# KGGR_wD_FIX.net
KiCad netlist of a schematic drawn in EAGLE
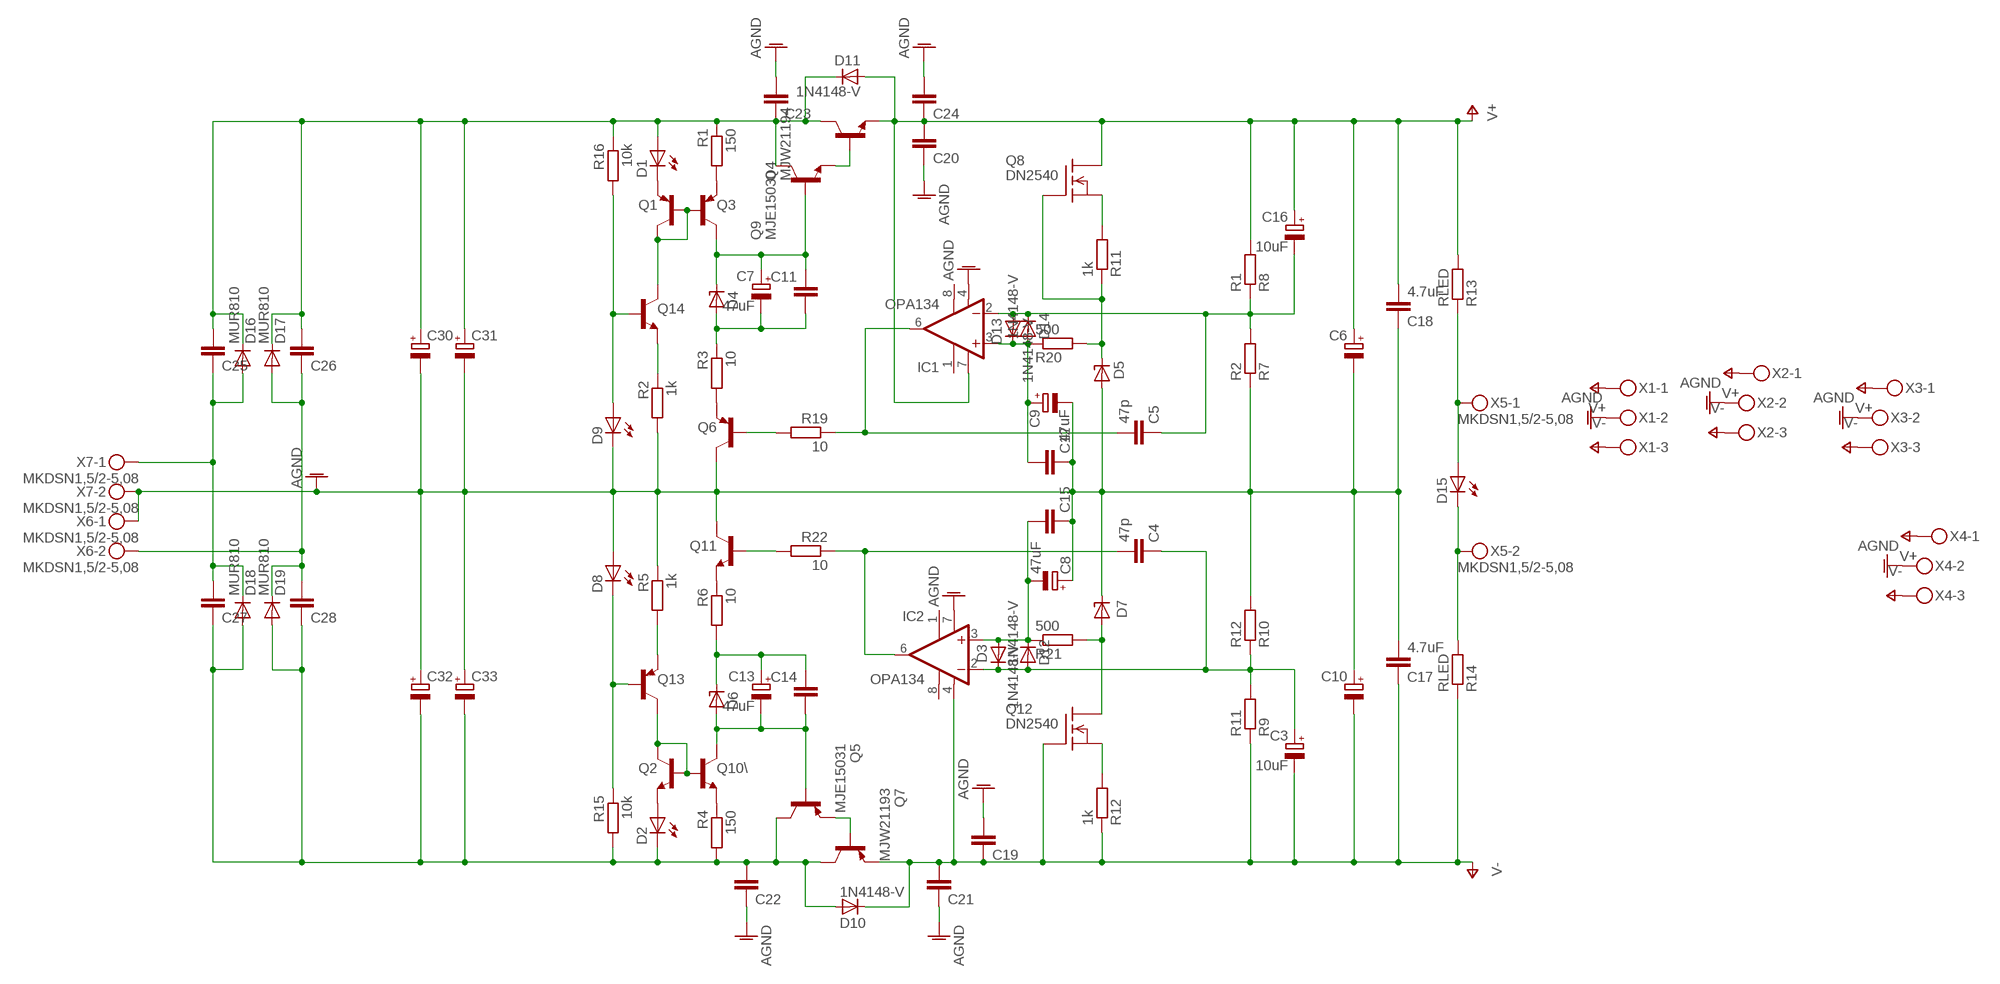
[diagram p0: schematic, sheet 1]
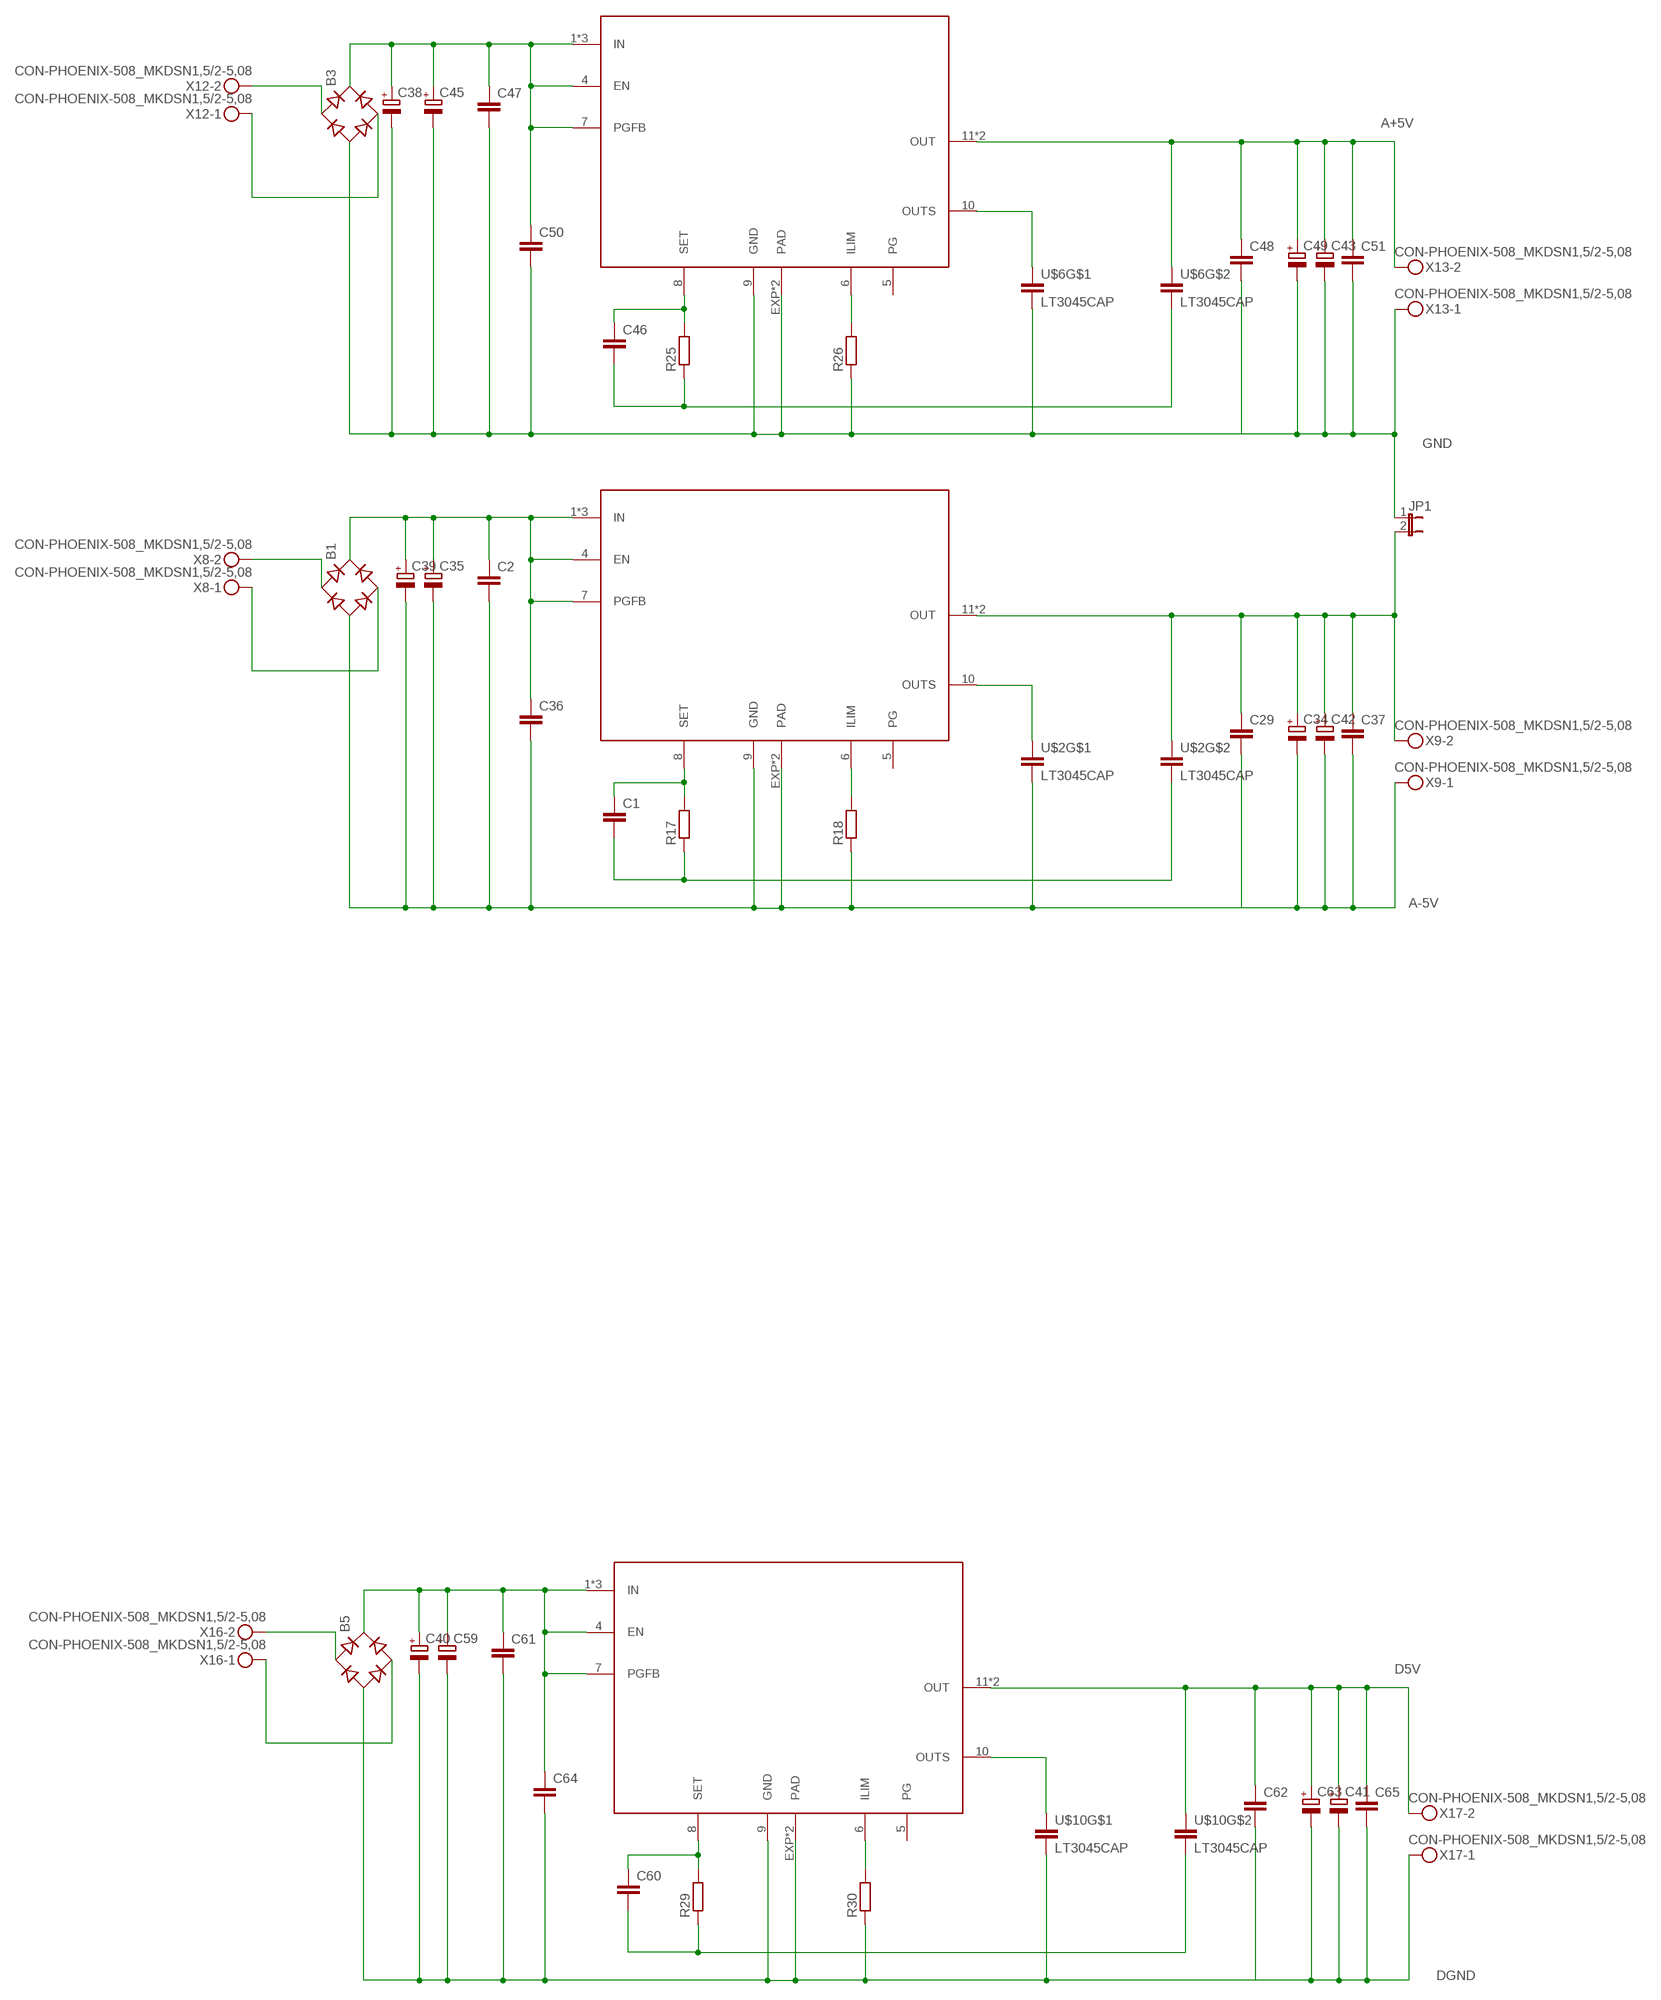
[diagram p1: schematic, sheet 2]

(export (version "E")
  (design (tool "Eeschema 10.0.6"))
  (components
    (comp (ref "C3")
      (value "10uF")
      (footprint "eagle-import:E5-8,5")
      (libsource (lib "eagle-import") (part "CPOL-EUE5-8.5"))
    )
    (comp (ref "C4")
      (value "47p")
      (footprint "eagle-import:C025_050-025X075")
      (libsource (lib "eagle-import") (part "C-EU025_050-025X075"))
    )
    (comp (ref "C5")
      (value "47p")
      (footprint "eagle-import:C025_050-025X075")
      (libsource (lib "eagle-import") (part "C-EU025_050-025X075"))
    )
    (comp (ref "C6")
      (value "CPOL-EUE7.5-18")
      (footprint "eagle-import:E7,5-18")
      (libsource (lib "eagle-import") (part "CPOL-EUE7.5-18"))
    )
    (comp (ref "C7")
      (value "47uF")
      (footprint "eagle-import:E5-8,5")
      (libsource (lib "eagle-import") (part "CPOL-EUE5-8.5"))
    )
    (comp (ref "C8")
      (value "47uF")
      (footprint "eagle-import:E5-8,5")
      (libsource (lib "eagle-import") (part "CPOL-EUE5-8.5"))
    )
    (comp (ref "C9")
      (value "47uF")
      (footprint "eagle-import:E5-8,5")
      (libsource (lib "eagle-import") (part "CPOL-EUE5-8.5"))
    )
    (comp (ref "C10")
      (value "CPOL-EUE7.5-18")
      (footprint "eagle-import:E7,5-18")
      (libsource (lib "eagle-import") (part "CPOL-EUE7.5-18"))
    )
    (comp (ref "C11")
      (value "C-EU050-035X075")
      (footprint "eagle-import:C050-035X075")
      (libsource (lib "eagle-import") (part "C-EU050-035X075"))
    )
    (comp (ref "C12")
      (value "C-EU050-035X075")
      (footprint "eagle-import:C050-035X075")
      (libsource (lib "eagle-import") (part "C-EU050-035X075"))
    )
    (comp (ref "C13")
      (value "47uF")
      (footprint "eagle-import:E5-8,5")
      (libsource (lib "eagle-import") (part "CPOL-EUE5-8.5"))
    )
    (comp (ref "C14")
      (value "C-EU050-035X075")
      (footprint "eagle-import:C050-035X075")
      (libsource (lib "eagle-import") (part "C-EU050-035X075"))
    )
    (comp (ref "C15")
      (value "C-EU050-035X075")
      (footprint "eagle-import:C050-035X075")
      (libsource (lib "eagle-import") (part "C-EU050-035X075"))
    )
    (comp (ref "C16")
      (value "10uF")
      (footprint "eagle-import:E5-8,5")
      (libsource (lib "eagle-import") (part "CPOL-EUE5-8.5"))
    )
    (comp (ref "C17")
      (value "4.7uF")
      (footprint "eagle-import:C050-075X075")
      (libsource (lib "eagle-import") (part "C-EU050-075X075"))
    )
    (comp (ref "C18")
      (value "4.7uF")
      (footprint "eagle-import:C050-075X075")
      (libsource (lib "eagle-import") (part "C-EU050-075X075"))
    )
    (comp (ref "C19")
      (value "C-EU050-035X075")
      (footprint "eagle-import:C050-035X075")
      (libsource (lib "eagle-import") (part "C-EU050-035X075"))
    )
    (comp (ref "C20")
      (value "C-EU050-035X075")
      (footprint "eagle-import:C050-035X075")
      (libsource (lib "eagle-import") (part "C-EU050-035X075"))
    )
    (comp (ref "C21")
      (value "C-EU050-035X075")
      (footprint "eagle-import:C050-035X075")
      (libsource (lib "eagle-import") (part "C-EU050-035X075"))
    )
    (comp (ref "C22")
      (value "C-EU050-075X075")
      (footprint "eagle-import:C050-075X075")
      (libsource (lib "eagle-import") (part "C-EU050-075X075"))
    )
    (comp (ref "C23")
      (value "C-EU050-075X075")
      (footprint "eagle-import:C050-075X075")
      (libsource (lib "eagle-import") (part "C-EU050-075X075"))
    )
    (comp (ref "C24")
      (value "C-EU050-035X075")
      (footprint "eagle-import:C050-035X075")
      (libsource (lib "eagle-import") (part "C-EU050-035X075"))
    )
    (comp (ref "C25")
      (value "C-EU050-035X075")
      (footprint "eagle-import:C050-035X075")
      (libsource (lib "eagle-import") (part "C-EU050-035X075"))
    )
    (comp (ref "C26")
      (value "C-EU050-035X075")
      (footprint "eagle-import:C050-035X075")
      (libsource (lib "eagle-import") (part "C-EU050-035X075"))
    )
    (comp (ref "C27")
      (value "C-EU050-035X075")
      (footprint "eagle-import:C050-035X075")
      (libsource (lib "eagle-import") (part "C-EU050-035X075"))
    )
    (comp (ref "C28")
      (value "C-EU050-035X075")
      (footprint "eagle-import:C050-035X075")
      (libsource (lib "eagle-import") (part "C-EU050-035X075"))
    )
    (comp (ref "C30")
      (value "CPOL-EUE7.5-18")
      (footprint "eagle-import:E7,5-18")
      (libsource (lib "eagle-import") (part "CPOL-EUE7.5-18"))
    )
    (comp (ref "C31")
      (value "CPOL-EUE7.5-18")
      (footprint "eagle-import:E7,5-18")
      (libsource (lib "eagle-import") (part "CPOL-EUE7.5-18"))
    )
    (comp (ref "C32")
      (value "CPOL-EUE7.5-18")
      (footprint "eagle-import:E7,5-18")
      (libsource (lib "eagle-import") (part "CPOL-EUE7.5-18"))
    )
    (comp (ref "C33")
      (value "CPOL-EUE7.5-18")
      (footprint "eagle-import:E7,5-18")
      (libsource (lib "eagle-import") (part "CPOL-EUE7.5-18"))
    )
    (comp (ref "D1")
      (value "LED5MM")
      (footprint "eagle-import:LED5MM")
      (libsource (lib "eagle-import") (part "LED5MM"))
    )
    (comp (ref "D2")
      (value "LED5MM")
      (footprint "eagle-import:LED5MM")
      (libsource (lib "eagle-import") (part "LED5MM"))
    )
    (comp (ref "D3")
      (value "1N4148-V")
      (footprint "eagle-import:1N4148")
      (libsource (lib "eagle-import") (part "1N4148-V"))
    )
    (comp (ref "D4")
      (value "1N4728")
      (footprint "eagle-import:DO41Z10")
      (libsource (lib "eagle-import") (part "1N4728"))
    )
    (comp (ref "D5")
      (value "LT1021")
      (footprint "eagle-import:DIL08")
      (libsource (lib "eagle-import") (part "LT1021-V"))
    )
    (comp (ref "D6")
      (value "1N4728")
      (footprint "eagle-import:DO41Z10")
      (libsource (lib "eagle-import") (part "1N4728"))
    )
    (comp (ref "D7")
      (value "LT1021")
      (footprint "eagle-import:DIL08")
      (libsource (lib "eagle-import") (part "LT1021-V"))
    )
    (comp (ref "D8")
      (value "LED5MM")
      (footprint "eagle-import:LED5MM")
      (libsource (lib "eagle-import") (part "LED5MM"))
    )
    (comp (ref "D9")
      (value "LED5MM")
      (footprint "eagle-import:LED5MM")
      (libsource (lib "eagle-import") (part "LED5MM"))
    )
    (comp (ref "D10")
      (value "1N4148-V")
      (footprint "eagle-import:1N4148")
      (libsource (lib "eagle-import") (part "1N4148-V"))
    )
    (comp (ref "D11")
      (value "1N4148-V")
      (footprint "eagle-import:1N4148")
      (libsource (lib "eagle-import") (part "1N4148-V"))
    )
    (comp (ref "D12")
      (value "1N4148-V")
      (footprint "eagle-import:1N4148")
      (libsource (lib "eagle-import") (part "1N4148-V"))
    )
    (comp (ref "D13")
      (value "1N4148-V")
      (footprint "eagle-import:1N4148")
      (libsource (lib "eagle-import") (part "1N4148-V"))
    )
    (comp (ref "D14")
      (value "1N4148-V")
      (footprint "eagle-import:1N4148")
      (libsource (lib "eagle-import") (part "1N4148-V"))
    )
    (comp (ref "D15")
      (value "LED5MM")
      (footprint "eagle-import:LED5MM")
      (libsource (lib "eagle-import") (part "LED5MM"))
    )
    (comp (ref "D16")
      (value "MUR810")
      (footprint "eagle-import:TO220ACS")
      (libsource (lib "eagle-import") (part "MUR810"))
    )
    (comp (ref "D17")
      (value "MUR810")
      (footprint "eagle-import:TO220ACS")
      (libsource (lib "eagle-import") (part "MUR810"))
    )
    (comp (ref "D18")
      (value "MUR810")
      (footprint "eagle-import:TO220ACS")
      (libsource (lib "eagle-import") (part "MUR810"))
    )
    (comp (ref "D19")
      (value "MUR810")
      (footprint "eagle-import:TO220ACS")
      (libsource (lib "eagle-import") (part "MUR810"))
    )
    (comp (ref "IC1")
      (value "OPA134")
      (footprint "eagle-import:DIL08")
      (fields (field (name "MF") "TEXAS INSTRUMENTS") (field (name "MPN") "OPA134PA"))
      (libsource (lib "eagle-import") (part "OPA134P"))
    )
    (comp (ref "IC2")
      (value "OPA134")
      (footprint "eagle-import:DIL08")
      (fields (field (name "MF") "TEXAS INSTRUMENTS") (field (name "MPN") "OPA134PA"))
      (libsource (lib "eagle-import") (part "OPA134P"))
    )
    (comp (ref "Q1")
      (value "MPSA92-PNP-TO92-EBC")
      (footprint "eagle-import:TO92-EBC")
      (libsource (lib "eagle-import") (part "-PNP-TO92-EBCMPSA92"))
    )
    (comp (ref "Q2")
      (value "MPSA42-NPN-TO92-EBC")
      (footprint "eagle-import:TO92-EBC")
      (libsource (lib "eagle-import") (part "-NPN-TO92-EBCMPSA42"))
    )
    (comp (ref "Q3")
      (value "MPSA92-PNP-TO92-EBC")
      (footprint "eagle-import:TO92-EBC")
      (libsource (lib "eagle-import") (part "-PNP-TO92-EBCMPSA92"))
    )
    (comp (ref "Q4")
      (value "MJW21194")
      (footprint "eagle-import:TO-264")
      (libsource (lib "eagle-import") (part "MJL4281"))
    )
    (comp (ref "Q5")
      (value "MJE15031")
      (footprint "eagle-import:TO220KG")
      (libsource (lib "eagle-import") (part "MJE15031"))
    )
    (comp (ref "Q6")
      (value "MPSA92-PNP-TO92-EBC")
      (footprint "eagle-import:TO92-EBC")
      (libsource (lib "eagle-import") (part "-PNP-TO92-EBCMPSA92"))
    )
    (comp (ref "Q7")
      (value "MJW21193")
      (footprint "eagle-import:TO-264")
      (libsource (lib "eagle-import") (part "MJL4302"))
    )
    (comp (ref "Q8")
      (value "DN2540")
      (footprint "eagle-import:TO92-")
      (libsource (lib "eagle-import") (part "2N7000"))
    )
    (comp (ref "Q9")
      (value "MJE15030")
      (footprint "eagle-import:TO220KG")
      (libsource (lib "eagle-import") (part "MJE15030"))
    )
    (comp (ref "Q10\\")
      (value "MPSA42-NPN-TO92-EBC")
      (footprint "eagle-import:TO92-EBC")
      (libsource (lib "eagle-import") (part "-NPN-TO92-EBCMPSA42"))
    )
    (comp (ref "Q11")
      (value "MPSA42-NPN-TO92-EBC")
      (footprint "eagle-import:TO92-EBC")
      (libsource (lib "eagle-import") (part "-NPN-TO92-EBCMPSA42"))
    )
    (comp (ref "Q12")
      (value "DN2540")
      (footprint "eagle-import:TO92-")
      (libsource (lib "eagle-import") (part "2N7000"))
    )
    (comp (ref "Q13")
      (value "MPSA92-PNP-TO92-EBC")
      (footprint "eagle-import:TO92-EBC")
      (libsource (lib "eagle-import") (part "-PNP-TO92-EBCMPSA92"))
    )
    (comp (ref "Q14")
      (value "MPSA42-NPN-TO92-EBC")
      (footprint "eagle-import:TO92-EBC")
      (libsource (lib "eagle-import") (part "-NPN-TO92-EBCMPSA42"))
    )
    (comp (ref "R1")
      (value "150")
      (footprint "eagle-import:0309_12")
      (libsource (lib "eagle-import") (part "R-EU_0309/12"))
    )
    (comp (ref "R2")
      (value "1k")
      (footprint "eagle-import:0309_12")
      (libsource (lib "eagle-import") (part "R-EU_0309/12"))
    )
    (comp (ref "R3")
      (value "10")
      (footprint "eagle-import:0309_12")
      (libsource (lib "eagle-import") (part "R-EU_0309/12"))
    )
    (comp (ref "R4")
      (value "150")
      (footprint "eagle-import:0309_12")
      (libsource (lib "eagle-import") (part "R-EU_0309/12"))
    )
    (comp (ref "R5")
      (value "1k")
      (footprint "eagle-import:0309_12")
      (libsource (lib "eagle-import") (part "R-EU_0309/12"))
    )
    (comp (ref "R6")
      (value "10")
      (footprint "eagle-import:0309_12")
      (libsource (lib "eagle-import") (part "R-EU_0309/12"))
    )
    (comp (ref "R7")
      (value "R2")
      (footprint "eagle-import:0309_12")
      (libsource (lib "eagle-import") (part "R-EU_0309/12"))
    )
    (comp (ref "R8")
      (value "R1")
      (footprint "eagle-import:0309_12")
      (libsource (lib "eagle-import") (part "R-EU_0309/12"))
    )
    (comp (ref "R9")
      (value "R11")
      (footprint "eagle-import:0309_12")
      (libsource (lib "eagle-import") (part "R-EU_0309/12"))
    )
    (comp (ref "R10")
      (value "R12")
      (footprint "eagle-import:0309_12")
      (libsource (lib "eagle-import") (part "R-EU_0309/12"))
    )
    (comp (ref "R11")
      (value "1k")
      (footprint "eagle-import:0309_12")
      (libsource (lib "eagle-import") (part "R-EU_0309/12"))
    )
    (comp (ref "R12")
      (value "1k")
      (footprint "eagle-import:0309_12")
      (libsource (lib "eagle-import") (part "R-EU_0309/12"))
    )
    (comp (ref "R13")
      (value "RLED")
      (footprint "eagle-import:0309_12")
      (libsource (lib "eagle-import") (part "R-EU_0309/12"))
    )
    (comp (ref "R14")
      (value "RLED")
      (footprint "eagle-import:0309_12")
      (libsource (lib "eagle-import") (part "R-EU_0309/12"))
    )
    (comp (ref "R15")
      (value "10k")
      (footprint "eagle-import:0309_12")
      (libsource (lib "eagle-import") (part "R-EU_0309/12"))
    )
    (comp (ref "R16")
      (value "10k")
      (footprint "eagle-import:0309_12")
      (libsource (lib "eagle-import") (part "R-EU_0309/12"))
    )
    (comp (ref "R19")
      (value "10")
      (footprint "eagle-import:0309_12")
      (libsource (lib "eagle-import") (part "R-EU_0309/12"))
    )
    (comp (ref "R20")
      (value "500")
      (footprint "eagle-import:0309_12")
      (libsource (lib "eagle-import") (part "R-EU_0309/12"))
    )
    (comp (ref "R21")
      (value "500")
      (footprint "eagle-import:0309_12")
      (libsource (lib "eagle-import") (part "R-EU_0309/12"))
    )
    (comp (ref "R22")
      (value "10")
      (footprint "eagle-import:0309_12")
      (libsource (lib "eagle-import") (part "R-EU_0309/12"))
    )
    (comp (ref "X1")
      (value "MKDSN1,5/3-5,08")
      (footprint "eagle-import:MKDSN1,5_3-5,08")
      (libsource (lib "eagle-import") (part "MKDSN1,5/3-5,08"))
    )
    (comp (ref "X2")
      (value "MKDSN1,5/3-5,08")
      (footprint "eagle-import:MKDSN1,5_3-5,08")
      (libsource (lib "eagle-import") (part "MKDSN1,5/3-5,08"))
    )
    (comp (ref "X3")
      (value "MKDSN1,5/3-5,08")
      (footprint "eagle-import:MKDSN1,5_3-5,08")
      (libsource (lib "eagle-import") (part "MKDSN1,5/3-5,08"))
    )
    (comp (ref "X4")
      (value "MKDSN1,5/3-5,08")
      (footprint "eagle-import:MKDSN1,5_3-5,08")
      (libsource (lib "eagle-import") (part "MKDSN1,5/3-5,08"))
    )
    (comp (ref "X5")
      (value "MKDSN1,5/2-5,08")
      (footprint "eagle-import:MKDSN1,5_2-5,08")
      (libsource (lib "eagle-import") (part "MKDSN1,5/2-5,08"))
    )
    (comp (ref "X6")
      (value "MKDSN1,5/2-5,08")
      (footprint "eagle-import:MKDSN1,5_2-5,08")
      (libsource (lib "eagle-import") (part "MKDSN1,5/2-5,08"))
    )
    (comp (ref "X7")
      (value "MKDSN1,5/2-5,08")
      (footprint "eagle-import:MKDSN1,5_2-5,08")
      (libsource (lib "eagle-import") (part "MKDSN1,5/2-5,08"))
    )
    (comp (ref "B1")
      (value "RB1A")
      (footprint "eagle-import:RB1A")
      (libsource (lib "eagle-import") (part "RB1A"))
    )
    (comp (ref "B3")
      (value "RB1A")
      (footprint "eagle-import:RB1A")
      (libsource (lib "eagle-import") (part "RB1A"))
    )
    (comp (ref "B5")
      (value "RB1A")
      (footprint "eagle-import:RB1A")
      (libsource (lib "eagle-import") (part "RB1A"))
    )
    (comp (ref "C1")
      (value "C-EUC1206")
      (footprint "eagle-import:C1206")
      (libsource (lib "eagle-import") (part "C-EUC1206"))
    )
    (comp (ref "C2")
      (value "C-EU050-050X075")
      (footprint "eagle-import:C050-050X075")
      (libsource (lib "eagle-import") (part "C-EU050-050X075"))
    )
    (comp (ref "C29")
      (value "C-EU050-050X075")
      (footprint "eagle-import:C050-050X075")
      (libsource (lib "eagle-import") (part "C-EU050-050X075"))
    )
    (comp (ref "C34")
      (value "CPOL-EUE5-10.5")
      (footprint "eagle-import:E5-10,5")
      (libsource (lib "eagle-import") (part "CPOL-EUE5-10.5"))
    )
    (comp (ref "C35")
      (value "CPOL-EUE7.5-18")
      (footprint "eagle-import:E7,5-18")
      (libsource (lib "eagle-import") (part "CPOL-EUE7.5-18"))
    )
    (comp (ref "C36")
      (value "C-EUC1206")
      (footprint "eagle-import:C1206")
      (libsource (lib "eagle-import") (part "C-EUC1206"))
    )
    (comp (ref "C37")
      (value "C-EUC1206")
      (footprint "eagle-import:C1206")
      (libsource (lib "eagle-import") (part "C-EUC1206"))
    )
    (comp (ref "C38")
      (value "CPOL-EUSP-CAP-CX")
      (footprint "eagle-import:SP-CAP-CX")
      (libsource (lib "eagle-import") (part "CPOL-EUSP-CAP-CX"))
    )
    (comp (ref "C39")
      (value "CPOL-EUSP-CAP-CX")
      (footprint "eagle-import:SP-CAP-CX")
      (libsource (lib "eagle-import") (part "CPOL-EUSP-CAP-CX"))
    )
    (comp (ref "C40")
      (value "CPOL-EUSP-CAP-CX")
      (footprint "eagle-import:SP-CAP-CX")
      (libsource (lib "eagle-import") (part "CPOL-EUSP-CAP-CX"))
    )
    (comp (ref "C41")
      (value "CPOL-EUSP-CAP-CX")
      (footprint "eagle-import:SP-CAP-CX")
      (libsource (lib "eagle-import") (part "CPOL-EUSP-CAP-CX"))
    )
    (comp (ref "C42")
      (value "CPOL-EUSP-CAP-CX")
      (footprint "eagle-import:SP-CAP-CX")
      (libsource (lib "eagle-import") (part "CPOL-EUSP-CAP-CX"))
    )
    (comp (ref "C43")
      (value "CPOL-EUSP-CAP-CX")
      (footprint "eagle-import:SP-CAP-CX")
      (libsource (lib "eagle-import") (part "CPOL-EUSP-CAP-CX"))
    )
    (comp (ref "C45")
      (value "CPOL-EUE7.5-18")
      (footprint "eagle-import:E7,5-18")
      (libsource (lib "eagle-import") (part "CPOL-EUE7.5-18"))
    )
    (comp (ref "C46")
      (value "C-EUC1206")
      (footprint "eagle-import:C1206")
      (libsource (lib "eagle-import") (part "C-EUC1206"))
    )
    (comp (ref "C47")
      (value "C-EU050-050X075")
      (footprint "eagle-import:C050-050X075")
      (libsource (lib "eagle-import") (part "C-EU050-050X075"))
    )
    (comp (ref "C48")
      (value "C-EU050-050X075")
      (footprint "eagle-import:C050-050X075")
      (libsource (lib "eagle-import") (part "C-EU050-050X075"))
    )
    (comp (ref "C49")
      (value "CPOL-EUE5-10.5")
      (footprint "eagle-import:E5-10,5")
      (libsource (lib "eagle-import") (part "CPOL-EUE5-10.5"))
    )
    (comp (ref "C50")
      (value "C-EUC1206")
      (footprint "eagle-import:C1206")
      (libsource (lib "eagle-import") (part "C-EUC1206"))
    )
    (comp (ref "C51")
      (value "C-EUC1206")
      (footprint "eagle-import:C1206")
      (libsource (lib "eagle-import") (part "C-EUC1206"))
    )
    (comp (ref "C59")
      (value "CPOL-EUE7.5-18")
      (footprint "eagle-import:E7,5-18")
      (libsource (lib "eagle-import") (part "CPOL-EUE7.5-18"))
    )
    (comp (ref "C60")
      (value "C-EUC1206")
      (footprint "eagle-import:C1206")
      (libsource (lib "eagle-import") (part "C-EUC1206"))
    )
    (comp (ref "C61")
      (value "C-EU050-050X075")
      (footprint "eagle-import:C050-050X075")
      (libsource (lib "eagle-import") (part "C-EU050-050X075"))
    )
    (comp (ref "C62")
      (value "C-EU050-050X075")
      (footprint "eagle-import:C050-050X075")
      (libsource (lib "eagle-import") (part "C-EU050-050X075"))
    )
    (comp (ref "C63")
      (value "CPOL-EUE5-10.5")
      (footprint "eagle-import:E5-10,5")
      (libsource (lib "eagle-import") (part "CPOL-EUE5-10.5"))
    )
    (comp (ref "C64")
      (value "C-EUC1206")
      (footprint "eagle-import:C1206")
      (libsource (lib "eagle-import") (part "C-EUC1206"))
    )
    (comp (ref "C65")
      (value "C-EUC1206")
      (footprint "eagle-import:C1206")
      (libsource (lib "eagle-import") (part "C-EUC1206"))
    )
    (comp (ref "JP1")
      (value "JP1E")
      (footprint "eagle-import:JP1")
      (libsource (lib "eagle-import") (part "JP1E"))
    )
    (comp (ref "R17")
      (value "R-EU_MELF0204R")
      (footprint "eagle-import:MINI_MELF-0204R")
      (libsource (lib "eagle-import") (part "R-EU_MELF0204R"))
    )
    (comp (ref "R18")
      (value "R-EU_MELF0204R")
      (footprint "eagle-import:MINI_MELF-0204R")
      (libsource (lib "eagle-import") (part "R-EU_MELF0204R"))
    )
    (comp (ref "R25")
      (value "R-EU_MELF0204R")
      (footprint "eagle-import:MINI_MELF-0204R")
      (libsource (lib "eagle-import") (part "R-EU_MELF0204R"))
    )
    (comp (ref "R26")
      (value "R-EU_MELF0204R")
      (footprint "eagle-import:MINI_MELF-0204R")
      (libsource (lib "eagle-import") (part "R-EU_MELF0204R"))
    )
    (comp (ref "R29")
      (value "R-EU_MELF0204R")
      (footprint "eagle-import:MINI_MELF-0204R")
      (libsource (lib "eagle-import") (part "R-EU_MELF0204R"))
    )
    (comp (ref "R30")
      (value "R-EU_MELF0204R")
      (footprint "eagle-import:MINI_MELF-0204R")
      (libsource (lib "eagle-import") (part "R-EU_MELF0204R"))
    )
    (comp (ref "U$1")
      (value "LT3045")
      (footprint "eagle-import:MSOP12")
      (libsource (lib "eagle-import") (part "LT3045"))
    )
    (comp (ref "U$2")
      (value "LT3045CAP")
      (footprint "eagle-import:LT3045CAP")
      (libsource (lib "eagle-import") (part "LT3045CAP"))
    )
    (comp (ref "U$5")
      (value "LT3045")
      (footprint "eagle-import:MSOP12")
      (libsource (lib "eagle-import") (part "LT3045"))
    )
    (comp (ref "U$6")
      (value "LT3045CAP")
      (footprint "eagle-import:LT3045CAP")
      (libsource (lib "eagle-import") (part "LT3045CAP"))
    )
    (comp (ref "U$9")
      (value "LT3045")
      (footprint "eagle-import:MSOP12")
      (libsource (lib "eagle-import") (part "LT3045"))
    )
    (comp (ref "U$10")
      (value "LT3045CAP")
      (footprint "eagle-import:LT3045CAP")
      (libsource (lib "eagle-import") (part "LT3045CAP"))
    )
    (comp (ref "X8")
      (value "CON-PHOENIX-508_MKDSN1,5/2-5,08")
      (footprint "eagle-import:CON-PHOENIX-508_MKDSN1,5_2-5,08")
      (libsource (lib "eagle-import") (part "CON-PHOENIX-508_MKDSN1,5/2-5,08"))
    )
    (comp (ref "X9")
      (value "CON-PHOENIX-508_MKDSN1,5/2-5,08")
      (footprint "eagle-import:CON-PHOENIX-508_MKDSN1,5_2-5,08")
      (libsource (lib "eagle-import") (part "CON-PHOENIX-508_MKDSN1,5/2-5,08"))
    )
    (comp (ref "X12")
      (value "CON-PHOENIX-508_MKDSN1,5/2-5,08")
      (footprint "eagle-import:CON-PHOENIX-508_MKDSN1,5_2-5,08")
      (libsource (lib "eagle-import") (part "CON-PHOENIX-508_MKDSN1,5/2-5,08"))
    )
    (comp (ref "X13")
      (value "CON-PHOENIX-508_MKDSN1,5/2-5,08")
      (footprint "eagle-import:CON-PHOENIX-508_MKDSN1,5_2-5,08")
      (libsource (lib "eagle-import") (part "CON-PHOENIX-508_MKDSN1,5/2-5,08"))
    )
    (comp (ref "X16")
      (value "CON-PHOENIX-508_MKDSN1,5/2-5,08")
      (footprint "eagle-import:CON-PHOENIX-508_MKDSN1,5_2-5,08")
      (libsource (lib "eagle-import") (part "CON-PHOENIX-508_MKDSN1,5/2-5,08"))
    )
    (comp (ref "X17")
      (value "CON-PHOENIX-508_MKDSN1,5/2-5,08")
      (footprint "eagle-import:CON-PHOENIX-508_MKDSN1,5_2-5,08")
      (libsource (lib "eagle-import") (part "CON-PHOENIX-508_MKDSN1,5/2-5,08"))
    )
  )
  (nets
    (net (code "1") (name "A+5V") (class "Default")
      (node (ref "C43") (pin "+") (pinfunction "+_+") (pintype "passive"))
      (node (ref "C48") (pin "1") (pinfunction "1_1") (pintype "passive"))
      (node (ref "C49") (pin "+") (pinfunction "+_+") (pintype "passive"))
      (node (ref "C51") (pin "1") (pinfunction "1_1") (pintype "passive"))
      (node (ref "U$5") (pin "11") (pinfunction "OUT_11") (pintype "bidirectional"))
      (node (ref "U$5") (pin "12") (pinfunction "OUT_12") (pintype "bidirectional"))
      (node (ref "U$6") (pin "4") (pinfunction "1_4") (pintype "passive"))
      (node (ref "X13") (pin "2") (pinfunction "KL_2") (pintype "passive"))
    )
    (net (code "2") (name "A-5V") (class "Default")
      (node (ref "B1") (pin "-") (pinfunction "-_-") (pintype "passive"))
      (node (ref "C2") (pin "2") (pinfunction "2_2") (pintype "passive"))
      (node (ref "C29") (pin "2") (pinfunction "2_2") (pintype "passive"))
      (node (ref "C34") (pin "-") (pinfunction "-_-") (pintype "passive"))
      (node (ref "C35") (pin "-") (pinfunction "-_-") (pintype "passive"))
      (node (ref "C36") (pin "2") (pinfunction "2_2") (pintype "passive"))
      (node (ref "C37") (pin "2") (pinfunction "2_2") (pintype "passive"))
      (node (ref "C39") (pin "-") (pinfunction "-_-") (pintype "passive"))
      (node (ref "C42") (pin "-") (pinfunction "-_-") (pintype "passive"))
      (node (ref "R18") (pin "1") (pinfunction "1_1") (pintype "passive"))
      (node (ref "U$1") (pin "9") (pinfunction "GND_9") (pintype "bidirectional"))
      (node (ref "U$1") (pin "EXP") (pinfunction "PAD_EXP") (pintype "bidirectional"))
      (node (ref "U$1") (pin "EXP1") (pinfunction "PAD_EXP1") (pintype "bidirectional"))
      (node (ref "U$2") (pin "5") (pinfunction "2_5") (pintype "passive"))
      (node (ref "X9") (pin "1") (pinfunction "KL_1") (pintype "passive"))
    )
    (net (code "3") (name "AGND") (class "Default")
      (node (ref "C10") (pin "+") (pinfunction "+_+") (pintype "passive"))
      (node (ref "C12") (pin "1") (pinfunction "1_1") (pintype "passive"))
      (node (ref "C15") (pin "1") (pinfunction "1_1") (pintype "passive"))
      (node (ref "C17") (pin "2") (pinfunction "2_2") (pintype "passive"))
      (node (ref "C18") (pin "1") (pinfunction "1_1") (pintype "passive"))
      (node (ref "C19") (pin "2") (pinfunction "2_2") (pintype "passive"))
      (node (ref "C20") (pin "1") (pinfunction "1_1") (pintype "passive"))
      (node (ref "C21") (pin "1") (pinfunction "1_1") (pintype "passive"))
      (node (ref "C22") (pin "1") (pinfunction "1_1") (pintype "passive"))
      (node (ref "C23") (pin "2") (pinfunction "2_2") (pintype "passive"))
      (node (ref "C24") (pin "2") (pinfunction "2_2") (pintype "passive"))
      (node (ref "C30") (pin "-") (pinfunction "-_-") (pintype "passive"))
      (node (ref "C31") (pin "-") (pinfunction "-_-") (pintype "passive"))
      (node (ref "C32") (pin "+") (pinfunction "+_+") (pintype "passive"))
      (node (ref "C33") (pin "+") (pinfunction "+_+") (pintype "passive"))
      (node (ref "C6") (pin "-") (pinfunction "-_-") (pintype "passive"))
      (node (ref "C8") (pin "+") (pinfunction "+_+") (pintype "passive"))
      (node (ref "C9") (pin "-") (pinfunction "-_-") (pintype "passive"))
      (node (ref "D5") (pin "4") (pinfunction "GND_4") (pintype "passive"))
      (node (ref "D7") (pin "6") (pinfunction "OUT_6") (pintype "passive"))
      (node (ref "D8") (pin "A") (pinfunction "A_A") (pintype "passive"))
      (node (ref "D9") (pin "K") (pinfunction "C_K") (pintype "passive"))
      (node (ref "IC1") (pin "4") (pinfunction "V-_4") (pintype "power_in"))
      (node (ref "IC2") (pin "7") (pinfunction "V+_7") (pintype "power_in"))
      (node (ref "Q11") (pin "C") (pinfunction "C_C") (pintype "passive"))
      (node (ref "Q6") (pin "C") (pinfunction "C_C") (pintype "passive"))
      (node (ref "R10") (pin "2") (pinfunction "2_2") (pintype "passive"))
      (node (ref "R2") (pin "2") (pinfunction "2_2") (pintype "passive"))
      (node (ref "R5") (pin "1") (pinfunction "1_1") (pintype "passive"))
      (node (ref "R7") (pin "1") (pinfunction "1_1") (pintype "passive"))
      (node (ref "X1") (pin "2") (pinfunction "KL_2") (pintype "passive"))
      (node (ref "X2") (pin "2") (pinfunction "KL_2") (pintype "passive"))
      (node (ref "X3") (pin "2") (pinfunction "KL_2") (pintype "passive"))
      (node (ref "X4") (pin "2") (pinfunction "KL_2") (pintype "passive"))
      (node (ref "X6") (pin "1") (pinfunction "KL_1") (pintype "passive"))
      (node (ref "X7") (pin "2") (pinfunction "KL_2") (pintype "passive"))
    )
    (net (code "4") (name "D5V") (class "Default")
      (node (ref "C41") (pin "+") (pinfunction "+_+") (pintype "passive"))
      (node (ref "C62") (pin "1") (pinfunction "1_1") (pintype "passive"))
      (node (ref "C63") (pin "+") (pinfunction "+_+") (pintype "passive"))
      (node (ref "C65") (pin "1") (pinfunction "1_1") (pintype "passive"))
      (node (ref "U$10") (pin "4") (pinfunction "1_4") (pintype "passive"))
      (node (ref "U$9") (pin "11") (pinfunction "OUT_11") (pintype "bidirectional"))
      (node (ref "U$9") (pin "12") (pinfunction "OUT_12") (pintype "bidirectional"))
      (node (ref "X17") (pin "2") (pinfunction "KL_2") (pintype "passive"))
    )
    (net (code "5") (name "DGND") (class "Default")
      (node (ref "B5") (pin "-") (pinfunction "-_-") (pintype "passive"))
      (node (ref "C40") (pin "-") (pinfunction "-_-") (pintype "passive"))
      (node (ref "C41") (pin "-") (pinfunction "-_-") (pintype "passive"))
      (node (ref "C59") (pin "-") (pinfunction "-_-") (pintype "passive"))
      (node (ref "C61") (pin "2") (pinfunction "2_2") (pintype "passive"))
      (node (ref "C62") (pin "2") (pinfunction "2_2") (pintype "passive"))
      (node (ref "C63") (pin "-") (pinfunction "-_-") (pintype "passive"))
      (node (ref "C64") (pin "2") (pinfunction "2_2") (pintype "passive"))
      (node (ref "C65") (pin "2") (pinfunction "2_2") (pintype "passive"))
      (node (ref "R30") (pin "1") (pinfunction "1_1") (pintype "passive"))
      (node (ref "U$10") (pin "5") (pinfunction "2_5") (pintype "passive"))
      (node (ref "U$9") (pin "9") (pinfunction "GND_9") (pintype "bidirectional"))
      (node (ref "U$9") (pin "EXP") (pinfunction "PAD_EXP") (pintype "bidirectional"))
      (node (ref "U$9") (pin "EXP1") (pinfunction "PAD_EXP1") (pintype "bidirectional"))
      (node (ref "X17") (pin "1") (pinfunction "KL_1") (pintype "passive"))
    )
    (net (code "6") (name "GND") (class "Default")
      (node (ref "B3") (pin "-") (pinfunction "-_-") (pintype "passive"))
      (node (ref "C38") (pin "-") (pinfunction "-_-") (pintype "passive"))
      (node (ref "C43") (pin "-") (pinfunction "-_-") (pintype "passive"))
      (node (ref "C45") (pin "-") (pinfunction "-_-") (pintype "passive"))
      (node (ref "C47") (pin "2") (pinfunction "2_2") (pintype "passive"))
      (node (ref "C48") (pin "2") (pinfunction "2_2") (pintype "passive"))
      (node (ref "C49") (pin "-") (pinfunction "-_-") (pintype "passive"))
      (node (ref "C50") (pin "2") (pinfunction "2_2") (pintype "passive"))
      (node (ref "C51") (pin "2") (pinfunction "2_2") (pintype "passive"))
      (node (ref "JP1") (pin "1") (pinfunction "1_1") (pintype "passive"))
      (node (ref "R26") (pin "1") (pinfunction "1_1") (pintype "passive"))
      (node (ref "U$5") (pin "9") (pinfunction "GND_9") (pintype "bidirectional"))
      (node (ref "U$5") (pin "EXP") (pinfunction "PAD_EXP") (pintype "bidirectional"))
      (node (ref "U$5") (pin "EXP1") (pinfunction "PAD_EXP1") (pintype "bidirectional"))
      (node (ref "U$6") (pin "5") (pinfunction "2_5") (pintype "passive"))
      (node (ref "X13") (pin "1") (pinfunction "KL_1") (pintype "passive"))
    )
    (net (code "7") (name "Net-(C11-Pad2)") (class "Default")
      (node (ref "C11") (pin "2") (pinfunction "2_2") (pintype "passive"))
      (node (ref "C7") (pin "-") (pinfunction "-_-") (pintype "passive"))
      (node (ref "D4") (pin "A") (pinfunction "A_A") (pintype "passive"))
      (node (ref "R3") (pin "1") (pinfunction "1_1") (pintype "passive"))
    )
    (net (code "8") (name "Net-(C13-Pad+)") (class "Default")
      (node (ref "C13") (pin "+") (pinfunction "+_+") (pintype "passive"))
      (node (ref "C14") (pin "1") (pinfunction "1_1") (pintype "passive"))
      (node (ref "D6") (pin "C") (pinfunction "C_C") (pintype "passive"))
      (node (ref "R6") (pin "2") (pinfunction "2_2") (pintype "passive"))
    )
    (net (code "9") (name "Net-(D1-C)") (class "Default")
      (node (ref "D1") (pin "K") (pinfunction "C_K") (pintype "passive"))
      (node (ref "Q1") (pin "E") (pinfunction "E_E") (pintype "passive"))
    )
    (net (code "10") (name "Net-(D2-C)") (class "Default")
      (node (ref "C22") (pin "2") (pinfunction "2_2") (pintype "passive"))
      (node (ref "C27") (pin "1") (pinfunction "1_1") (pintype "passive"))
      (node (ref "C28") (pin "1") (pinfunction "1_1") (pintype "passive"))
      (node (ref "C32") (pin "-") (pinfunction "-_-") (pintype "passive"))
      (node (ref "C33") (pin "-") (pinfunction "-_-") (pintype "passive"))
      (node (ref "D10") (pin "A") (pinfunction "A_A") (pintype "passive"))
      (node (ref "D18") (pin "A") (pinfunction "A_A") (pintype "passive"))
      (node (ref "D19") (pin "A") (pinfunction "A_A") (pintype "passive"))
      (node (ref "D2") (pin "K") (pinfunction "C_K") (pintype "passive"))
      (node (ref "Q5") (pin "2") (pinfunction "C_2") (pintype "passive"))
      (node (ref "Q7") (pin "C") (pinfunction "C_C") (pintype "passive"))
      (node (ref "R15") (pin "2") (pinfunction "2_2") (pintype "passive"))
      (node (ref "R4") (pin "2") (pinfunction "2_2") (pintype "passive"))
    )
    (net (code "11") (name "Net-(D2-PadA)") (class "Default")
      (node (ref "D2") (pin "A") (pinfunction "A_A") (pintype "passive"))
      (node (ref "Q2") (pin "E") (pinfunction "E_E") (pintype "passive"))
    )
    (net (code "12") (name "Net-(D5-OUT)") (class "Default")
      (node (ref "D5") (pin "6") (pinfunction "OUT_6") (pintype "passive"))
      (node (ref "Q8") (pin "2") (pinfunction "G_2") (pintype "passive"))
      (node (ref "R11") (pin "1") (pinfunction "1_1") (pintype "passive"))
      (node (ref "R20") (pin "2") (pinfunction "2_2") (pintype "passive"))
    )
    (net (code "13") (name "Net-(D7-GND)") (class "Default")
      (node (ref "D7") (pin "4") (pinfunction "GND_4") (pintype "passive"))
      (node (ref "Q12") (pin "1") (pinfunction "D_1") (pintype "passive"))
      (node (ref "R21") (pin "2") (pinfunction "2_2") (pintype "passive"))
    )
    (net (code "14") (name "Net-(D8-C)") (class "Default")
      (node (ref "D8") (pin "K") (pinfunction "C_K") (pintype "passive"))
      (node (ref "Q13") (pin "B") (pinfunction "B_B") (pintype "passive"))
      (node (ref "R15") (pin "1") (pinfunction "1_1") (pintype "passive"))
    )
    (net (code "15") (name "Net-(D9-PadA)") (class "Default")
      (node (ref "D9") (pin "A") (pinfunction "A_A") (pintype "passive"))
      (node (ref "Q14") (pin "B") (pinfunction "B_B") (pintype "passive"))
      (node (ref "R16") (pin "2") (pinfunction "2_2") (pintype "passive"))
    )
    (net (code "16") (name "Net-(D15-C)") (class "Default")
      (node (ref "D15") (pin "K") (pinfunction "C_K") (pintype "passive"))
      (node (ref "R14") (pin "2") (pinfunction "2_2") (pintype "passive"))
      (node (ref "X5") (pin "2") (pinfunction "KL_2") (pintype "passive"))
    )
    (net (code "17") (name "Net-(IC1-+IN)") (class "Default")
      (node (ref "C12") (pin "2") (pinfunction "2_2") (pintype "passive"))
      (node (ref "C9") (pin "+") (pinfunction "+_+") (pintype "passive"))
      (node (ref "D13") (pin "C") (pinfunction "C_C") (pintype "passive"))
      (node (ref "D14") (pin "A") (pinfunction "A_A") (pintype "passive"))
      (node (ref "IC1") (pin "3") (pinfunction "+IN_3") (pintype "input"))
      (node (ref "R20") (pin "1") (pinfunction "1_1") (pintype "passive"))
    )
    (net (code "18") (name "Net-(IC1--IN)") (class "Default")
      (node (ref "C16") (pin "-") (pinfunction "-_-") (pintype "passive"))
      (node (ref "C5") (pin "1") (pinfunction "1_1") (pintype "passive"))
      (node (ref "D13") (pin "A") (pinfunction "A_A") (pintype "passive"))
      (node (ref "D14") (pin "C") (pinfunction "C_C") (pintype "passive"))
      (node (ref "IC1") (pin "2") (pinfunction "-IN_2") (pintype "input"))
      (node (ref "R7") (pin "2") (pinfunction "2_2") (pintype "passive"))
      (node (ref "R8") (pin "1") (pinfunction "1_1") (pintype "passive"))
    )
    (net (code "19") (name "Net-(IC1-OUT)") (class "Default")
      (node (ref "C5") (pin "2") (pinfunction "2_2") (pintype "passive"))
      (node (ref "C5") (pin "3") (pinfunction "2_3") (pintype "passive"))
      (node (ref "IC1") (pin "6") (pinfunction "OUT_6") (pintype "output"))
      (node (ref "R19") (pin "1") (pinfunction "1_1") (pintype "passive"))
    )
    (net (code "20") (name "Net-(IC2-+IN)") (class "Default")
      (node (ref "C15") (pin "2") (pinfunction "2_2") (pintype "passive"))
      (node (ref "C8") (pin "-") (pinfunction "-_-") (pintype "passive"))
      (node (ref "D12") (pin "C") (pinfunction "C_C") (pintype "passive"))
      (node (ref "D3") (pin "A") (pinfunction "A_A") (pintype "passive"))
      (node (ref "IC2") (pin "3") (pinfunction "+IN_3") (pintype "input"))
      (node (ref "R21") (pin "1") (pinfunction "1_1") (pintype "passive"))
    )
    (net (code "21") (name "Net-(IC2--IN)") (class "Default")
      (node (ref "C3") (pin "+") (pinfunction "+_+") (pintype "passive"))
      (node (ref "C4") (pin "1") (pinfunction "1_1") (pintype "passive"))
      (node (ref "D12") (pin "A") (pinfunction "A_A") (pintype "passive"))
      (node (ref "D3") (pin "C") (pinfunction "C_C") (pintype "passive"))
      (node (ref "IC2") (pin "2") (pinfunction "-IN_2") (pintype "input"))
      (node (ref "R10") (pin "1") (pinfunction "1_1") (pintype "passive"))
      (node (ref "R9") (pin "2") (pinfunction "2_2") (pintype "passive"))
    )
    (net (code "22") (name "Net-(IC2-OUT)") (class "Default")
      (node (ref "C4") (pin "2") (pinfunction "2_2") (pintype "passive"))
      (node (ref "C4") (pin "3") (pinfunction "2_3") (pintype "passive"))
      (node (ref "IC2") (pin "6") (pinfunction "OUT_6") (pintype "output"))
      (node (ref "R22") (pin "1") (pinfunction "1_1") (pintype "passive"))
    )
    (net (code "23") (name "Net-(Q1-PadB)") (class "Default")
      (node (ref "Q1") (pin "B") (pinfunction "B_B") (pintype "passive"))
      (node (ref "Q1") (pin "C") (pinfunction "C_C") (pintype "passive"))
      (node (ref "Q14") (pin "C") (pinfunction "C_C") (pintype "passive"))
      (node (ref "Q3") (pin "B") (pinfunction "B_B") (pintype "passive"))
    )
    (net (code "24") (name "Net-(Q3-PadE)") (class "Default")
      (node (ref "Q3") (pin "E") (pinfunction "E_E") (pintype "passive"))
      (node (ref "R1") (pin "2") (pinfunction "2_2") (pintype "passive"))
    )
    (net (code "25") (name "Net-(Q5-B)") (class "Default")
      (node (ref "C13") (pin "-") (pinfunction "-_-") (pintype "passive"))
      (node (ref "C14") (pin "2") (pinfunction "2_2") (pintype "passive"))
      (node (ref "D6") (pin "A") (pinfunction "A_A") (pintype "passive"))
      (node (ref "Q10\\") (pin "C") (pinfunction "C_C") (pintype "passive"))
      (node (ref "Q5") (pin "1") (pinfunction "B_1") (pintype "passive"))
    )
    (net (code "26") (name "Net-(Q5-E)") (class "Default")
      (node (ref "Q5") (pin "3") (pinfunction "E_3") (pintype "passive"))
      (node (ref "Q7") (pin "B") (pinfunction "B_B") (pintype "passive"))
    )
    (net (code "27") (name "Net-(Q6-PadB)") (class "Default")
      (node (ref "Q6") (pin "B") (pinfunction "B_B") (pintype "passive"))
      (node (ref "R19") (pin "2") (pinfunction "2_2") (pintype "passive"))
    )
    (net (code "28") (name "Net-(Q6-PadE)") (class "Default")
      (node (ref "Q6") (pin "E") (pinfunction "E_E") (pintype "passive"))
      (node (ref "R3") (pin "2") (pinfunction "2_2") (pintype "passive"))
    )
    (net (code "29") (name "Net-(Q8-S)") (class "Default")
      (node (ref "Q8") (pin "3") (pinfunction "S_3") (pintype "passive"))
      (node (ref "R11") (pin "2") (pinfunction "2_2") (pintype "passive"))
    )
    (net (code "30") (name "Net-(Q9-B)") (class "Default")
      (node (ref "C11") (pin "1") (pinfunction "1_1") (pintype "passive"))
      (node (ref "C7") (pin "+") (pinfunction "+_+") (pintype "passive"))
      (node (ref "D4") (pin "C") (pinfunction "C_C") (pintype "passive"))
      (node (ref "Q3") (pin "C") (pinfunction "C_C") (pintype "passive"))
      (node (ref "Q9") (pin "1") (pinfunction "B_1") (pintype "passive"))
    )
    (net (code "31") (name "Net-(Q9-C)") (class "Default")
      (node (ref "C23") (pin "1") (pinfunction "1_1") (pintype "passive"))
      (node (ref "C25") (pin "2") (pinfunction "2_2") (pintype "passive"))
      (node (ref "C26") (pin "2") (pinfunction "2_2") (pintype "passive"))
      (node (ref "C30") (pin "+") (pinfunction "+_+") (pintype "passive"))
      (node (ref "C31") (pin "+") (pinfunction "+_+") (pintype "passive"))
      (node (ref "D1") (pin "A") (pinfunction "A_A") (pintype "passive"))
      (node (ref "D11") (pin "C") (pinfunction "C_C") (pintype "passive"))
      (node (ref "D16") (pin "C") (pinfunction "C_C") (pintype "passive"))
      (node (ref "D17") (pin "C") (pinfunction "C_C") (pintype "passive"))
      (node (ref "Q4") (pin "C") (pinfunction "C_C") (pintype "passive"))
      (node (ref "Q9") (pin "2") (pinfunction "C_2") (pintype "passive"))
      (node (ref "R1") (pin "1") (pinfunction "1_1") (pintype "passive"))
      (node (ref "R16") (pin "1") (pinfunction "1_1") (pintype "passive"))
    )
    (net (code "32") (name "Net-(Q9-E)") (class "Default")
      (node (ref "Q4") (pin "B") (pinfunction "B_B") (pintype "passive"))
      (node (ref "Q9") (pin "3") (pinfunction "E_3") (pintype "passive"))
    )
    (net (code "33") (name "Net-(Q10\\-PadB)") (class "Default")
      (node (ref "Q10\\") (pin "B") (pinfunction "B_B") (pintype "passive"))
      (node (ref "Q13") (pin "C") (pinfunction "C_C") (pintype "passive"))
      (node (ref "Q2") (pin "B") (pinfunction "B_B") (pintype "passive"))
      (node (ref "Q2") (pin "C") (pinfunction "C_C") (pintype "passive"))
    )
    (net (code "34") (name "Net-(Q10\\-PadE)") (class "Default")
      (node (ref "Q10\\") (pin "E") (pinfunction "E_E") (pintype "passive"))
      (node (ref "R4") (pin "1") (pinfunction "1_1") (pintype "passive"))
    )
    (net (code "35") (name "Net-(Q11-PadB)") (class "Default")
      (node (ref "Q11") (pin "B") (pinfunction "B_B") (pintype "passive"))
      (node (ref "R22") (pin "2") (pinfunction "2_2") (pintype "passive"))
    )
    (net (code "36") (name "Net-(Q11-PadE)") (class "Default")
      (node (ref "Q11") (pin "E") (pinfunction "E_E") (pintype "passive"))
      (node (ref "R6") (pin "1") (pinfunction "1_1") (pintype "passive"))
    )
    (net (code "37") (name "Net-(Q12-S)") (class "Default")
      (node (ref "Q12") (pin "3") (pinfunction "S_3") (pintype "passive"))
      (node (ref "R12") (pin "2") (pinfunction "2_2") (pintype "passive"))
    )
    (net (code "38") (name "Net-(Q13-PadE)") (class "Default")
      (node (ref "Q13") (pin "E") (pinfunction "E_E") (pintype "passive"))
      (node (ref "R5") (pin "2") (pinfunction "2_2") (pintype "passive"))
    )
    (net (code "39") (name "Net-(Q14-PadE)") (class "Default")
      (node (ref "Q14") (pin "E") (pinfunction "E_E") (pintype "passive"))
      (node (ref "R2") (pin "1") (pinfunction "1_1") (pintype "passive"))
    )
    (net (code "40") (name "Net-(U$1-EN)") (class "Default")
      (node (ref "B1") (pin "+") (pinfunction "+_+") (pintype "passive"))
      (node (ref "C2") (pin "1") (pinfunction "1_1") (pintype "passive"))
      (node (ref "C35") (pin "+") (pinfunction "+_+") (pintype "passive"))
      (node (ref "C36") (pin "1") (pinfunction "1_1") (pintype "passive"))
      (node (ref "C39") (pin "+") (pinfunction "+_+") (pintype "passive"))
      (node (ref "U$1") (pin "1") (pinfunction "IN_1") (pintype "bidirectional"))
      (node (ref "U$1") (pin "2") (pinfunction "IN_2") (pintype "bidirectional"))
      (node (ref "U$1") (pin "3") (pinfunction "IN_3") (pintype "bidirectional"))
      (node (ref "U$1") (pin "4") (pinfunction "EN_4") (pintype "bidirectional"))
      (node (ref "U$1") (pin "7") (pinfunction "PGFB_7") (pintype "bidirectional"))
    )
    (net (code "41") (name "Net-(U$1-ILIM)") (class "Default")
      (node (ref "R18") (pin "2") (pinfunction "2_2") (pintype "passive"))
      (node (ref "U$1") (pin "6") (pinfunction "ILIM_6") (pintype "bidirectional"))
    )
    (net (code "42") (name "Net-(U$1-OUTS)") (class "Default")
      (node (ref "U$1") (pin "10") (pinfunction "OUTS_10") (pintype "bidirectional"))
      (node (ref "U$2") (pin "3") (pinfunction "1_3") (pintype "passive"))
    )
    (net (code "43") (name "Net-(U$1-SET)") (class "Default")
      (node (ref "C1") (pin "1") (pinfunction "1_1") (pintype "passive"))
      (node (ref "R17") (pin "2") (pinfunction "2_2") (pintype "passive"))
      (node (ref "U$1") (pin "8") (pinfunction "SET_8") (pintype "bidirectional"))
    )
    (net (code "44") (name "Net-(U$2B-1)") (class "Default")
      (node (ref "C29") (pin "1") (pinfunction "1_1") (pintype "passive"))
      (node (ref "C34") (pin "+") (pinfunction "+_+") (pintype "passive"))
      (node (ref "C37") (pin "1") (pinfunction "1_1") (pintype "passive"))
      (node (ref "C42") (pin "+") (pinfunction "+_+") (pintype "passive"))
      (node (ref "JP1") (pin "2") (pinfunction "2_2") (pintype "passive"))
      (node (ref "U$1") (pin "11") (pinfunction "OUT_11") (pintype "bidirectional"))
      (node (ref "U$1") (pin "12") (pinfunction "OUT_12") (pintype "bidirectional"))
      (node (ref "U$2") (pin "4") (pinfunction "1_4") (pintype "passive"))
      (node (ref "X9") (pin "2") (pinfunction "KL_2") (pintype "passive"))
    )
    (net (code "45") (name "Net-(U$2B-2)") (class "Default")
      (node (ref "C1") (pin "2") (pinfunction "2_2") (pintype "passive"))
      (node (ref "R17") (pin "1") (pinfunction "1_1") (pintype "passive"))
      (node (ref "U$2") (pin "6") (pinfunction "2_6") (pintype "passive"))
    )
    (net (code "46") (name "Net-(U$5-EN)") (class "Default")
      (node (ref "B3") (pin "+") (pinfunction "+_+") (pintype "passive"))
      (node (ref "C38") (pin "+") (pinfunction "+_+") (pintype "passive"))
      (node (ref "C45") (pin "+") (pinfunction "+_+") (pintype "passive"))
      (node (ref "C47") (pin "1") (pinfunction "1_1") (pintype "passive"))
      (node (ref "C50") (pin "1") (pinfunction "1_1") (pintype "passive"))
      (node (ref "U$5") (pin "1") (pinfunction "IN_1") (pintype "bidirectional"))
      (node (ref "U$5") (pin "2") (pinfunction "IN_2") (pintype "bidirectional"))
      (node (ref "U$5") (pin "3") (pinfunction "IN_3") (pintype "bidirectional"))
      (node (ref "U$5") (pin "4") (pinfunction "EN_4") (pintype "bidirectional"))
      (node (ref "U$5") (pin "7") (pinfunction "PGFB_7") (pintype "bidirectional"))
    )
    (net (code "47") (name "Net-(U$5-ILIM)") (class "Default")
      (node (ref "R26") (pin "2") (pinfunction "2_2") (pintype "passive"))
      (node (ref "U$5") (pin "6") (pinfunction "ILIM_6") (pintype "bidirectional"))
    )
    (net (code "48") (name "Net-(U$5-OUTS)") (class "Default")
      (node (ref "U$5") (pin "10") (pinfunction "OUTS_10") (pintype "bidirectional"))
      (node (ref "U$6") (pin "3") (pinfunction "1_3") (pintype "passive"))
    )
    (net (code "49") (name "Net-(U$5-SET)") (class "Default")
      (node (ref "C46") (pin "1") (pinfunction "1_1") (pintype "passive"))
      (node (ref "R25") (pin "2") (pinfunction "2_2") (pintype "passive"))
      (node (ref "U$5") (pin "8") (pinfunction "SET_8") (pintype "bidirectional"))
    )
    (net (code "50") (name "Net-(U$6B-2)") (class "Default")
      (node (ref "C46") (pin "2") (pinfunction "2_2") (pintype "passive"))
      (node (ref "R25") (pin "1") (pinfunction "1_1") (pintype "passive"))
      (node (ref "U$6") (pin "6") (pinfunction "2_6") (pintype "passive"))
    )
    (net (code "51") (name "Net-(U$9-EN)") (class "Default")
      (node (ref "B5") (pin "+") (pinfunction "+_+") (pintype "passive"))
      (node (ref "C40") (pin "+") (pinfunction "+_+") (pintype "passive"))
      (node (ref "C59") (pin "+") (pinfunction "+_+") (pintype "passive"))
      (node (ref "C61") (pin "1") (pinfunction "1_1") (pintype "passive"))
      (node (ref "C64") (pin "1") (pinfunction "1_1") (pintype "passive"))
      (node (ref "U$9") (pin "1") (pinfunction "IN_1") (pintype "bidirectional"))
      (node (ref "U$9") (pin "2") (pinfunction "IN_2") (pintype "bidirectional"))
      (node (ref "U$9") (pin "3") (pinfunction "IN_3") (pintype "bidirectional"))
      (node (ref "U$9") (pin "4") (pinfunction "EN_4") (pintype "bidirectional"))
      (node (ref "U$9") (pin "7") (pinfunction "PGFB_7") (pintype "bidirectional"))
    )
    (net (code "52") (name "Net-(U$9-ILIM)") (class "Default")
      (node (ref "R30") (pin "2") (pinfunction "2_2") (pintype "passive"))
      (node (ref "U$9") (pin "6") (pinfunction "ILIM_6") (pintype "bidirectional"))
    )
    (net (code "53") (name "Net-(U$9-SET)") (class "Default")
      (node (ref "C60") (pin "1") (pinfunction "1_1") (pintype "passive"))
      (node (ref "R29") (pin "2") (pinfunction "2_2") (pintype "passive"))
      (node (ref "U$9") (pin "8") (pinfunction "SET_8") (pintype "bidirectional"))
    )
    (net (code "54") (name "Net-(U$10A-1)") (class "Default")
      (node (ref "U$10") (pin "3") (pinfunction "1_3") (pintype "passive"))
      (node (ref "U$9") (pin "10") (pinfunction "OUTS_10") (pintype "bidirectional"))
    )
    (net (code "55") (name "Net-(U$10B-2)") (class "Default")
      (node (ref "C60") (pin "2") (pinfunction "2_2") (pintype "passive"))
      (node (ref "R29") (pin "1") (pinfunction "1_1") (pintype "passive"))
      (node (ref "U$10") (pin "6") (pinfunction "2_6") (pintype "passive"))
    )
    (net (code "56") (name "Net-(X5A-KL)") (class "Default")
      (node (ref "D15") (pin "A") (pinfunction "A_A") (pintype "passive"))
      (node (ref "R13") (pin "1") (pinfunction "1_1") (pintype "passive"))
      (node (ref "X5") (pin "1") (pinfunction "KL_1") (pintype "passive"))
    )
    (net (code "57") (name "Net-(X6B-KL)") (class "Default")
      (node (ref "C26") (pin "1") (pinfunction "1_1") (pintype "passive"))
      (node (ref "C28") (pin "2") (pinfunction "2_2") (pintype "passive"))
      (node (ref "D17") (pin "A") (pinfunction "A_A") (pintype "passive"))
      (node (ref "D19") (pin "C") (pinfunction "C_C") (pintype "passive"))
      (node (ref "X6") (pin "2") (pinfunction "KL_2") (pintype "passive"))
    )
    (net (code "58") (name "Net-(X7A-KL)") (class "Default")
      (node (ref "C25") (pin "1") (pinfunction "1_1") (pintype "passive"))
      (node (ref "C27") (pin "2") (pinfunction "2_2") (pintype "passive"))
      (node (ref "D16") (pin "A") (pinfunction "A_A") (pintype "passive"))
      (node (ref "D18") (pin "C") (pinfunction "C_C") (pintype "passive"))
      (node (ref "X7") (pin "1") (pinfunction "KL_1") (pintype "passive"))
    )
    (net (code "59") (name "Net-(X8A-KL)") (class "Default")
      (node (ref "B1") (pin "AC2") (pinfunction "AC2_AC2") (pintype "passive"))
      (node (ref "X8") (pin "1") (pinfunction "KL_1") (pintype "passive"))
    )
    (net (code "60") (name "Net-(X8B-KL)") (class "Default")
      (node (ref "B1") (pin "AC1") (pinfunction "AC1_AC1") (pintype "passive"))
      (node (ref "X8") (pin "2") (pinfunction "KL_2") (pintype "passive"))
    )
    (net (code "61") (name "Net-(X12A-KL)") (class "Default")
      (node (ref "B3") (pin "AC2") (pinfunction "AC2_AC2") (pintype "passive"))
      (node (ref "X12") (pin "1") (pinfunction "KL_1") (pintype "passive"))
    )
    (net (code "62") (name "Net-(X12B-KL)") (class "Default")
      (node (ref "B3") (pin "AC1") (pinfunction "AC1_AC1") (pintype "passive"))
      (node (ref "X12") (pin "2") (pinfunction "KL_2") (pintype "passive"))
    )
    (net (code "63") (name "Net-(X16A-KL)") (class "Default")
      (node (ref "B5") (pin "AC2") (pinfunction "AC2_AC2") (pintype "passive"))
      (node (ref "X16") (pin "1") (pinfunction "KL_1") (pintype "passive"))
    )
    (net (code "64") (name "Net-(X16B-KL)") (class "Default")
      (node (ref "B5") (pin "AC1") (pinfunction "AC1_AC1") (pintype "passive"))
      (node (ref "X16") (pin "2") (pinfunction "KL_2") (pintype "passive"))
    )
    (net (code "65") (name "V+") (class "Default")
      (node (ref "C16") (pin "+") (pinfunction "+_+") (pintype "passive"))
      (node (ref "C18") (pin "2") (pinfunction "2_2") (pintype "passive"))
      (node (ref "C20") (pin "2") (pinfunction "2_2") (pintype "passive"))
      (node (ref "C24") (pin "1") (pinfunction "1_1") (pintype "passive"))
      (node (ref "C6") (pin "+") (pinfunction "+_+") (pintype "passive"))
      (node (ref "D11") (pin "A") (pinfunction "A_A") (pintype "passive"))
      (node (ref "IC1") (pin "7") (pinfunction "V+_7") (pintype "power_in"))
      (node (ref "Q4") (pin "E") (pinfunction "E_E") (pintype "passive"))
      (node (ref "Q8") (pin "1") (pinfunction "D_1") (pintype "passive"))
      (node (ref "R13") (pin "2") (pinfunction "2_2") (pintype "passive"))
      (node (ref "R8") (pin "2") (pinfunction "2_2") (pintype "passive"))
      (node (ref "X1") (pin "1") (pinfunction "KL_1") (pintype "passive"))
      (node (ref "X2") (pin "1") (pinfunction "KL_1") (pintype "passive"))
      (node (ref "X3") (pin "1") (pinfunction "KL_1") (pintype "passive"))
      (node (ref "X4") (pin "1") (pinfunction "KL_1") (pintype "passive"))
    )
    (net (code "66") (name "V-") (class "Default")
      (node (ref "C10") (pin "-") (pinfunction "-_-") (pintype "passive"))
      (node (ref "C17") (pin "1") (pinfunction "1_1") (pintype "passive"))
      (node (ref "C19") (pin "1") (pinfunction "1_1") (pintype "passive"))
      (node (ref "C21") (pin "2") (pinfunction "2_2") (pintype "passive"))
      (node (ref "C3") (pin "-") (pinfunction "-_-") (pintype "passive"))
      (node (ref "D10") (pin "C") (pinfunction "C_C") (pintype "passive"))
      (node (ref "IC2") (pin "4") (pinfunction "V-_4") (pintype "power_in"))
      (node (ref "Q12") (pin "2") (pinfunction "G_2") (pintype "passive"))
      (node (ref "Q7") (pin "E") (pinfunction "E_E") (pintype "passive"))
      (node (ref "R12") (pin "1") (pinfunction "1_1") (pintype "passive"))
      (node (ref "R14") (pin "1") (pinfunction "1_1") (pintype "passive"))
      (node (ref "R9") (pin "1") (pinfunction "1_1") (pintype "passive"))
      (node (ref "X1") (pin "3") (pinfunction "KL_3") (pintype "passive"))
      (node (ref "X2") (pin "3") (pinfunction "KL_3") (pintype "passive"))
      (node (ref "X3") (pin "3") (pinfunction "KL_3") (pintype "passive"))
      (node (ref "X4") (pin "3") (pinfunction "KL_3") (pintype "passive"))
    )
    (net (code "67") (name "unconnected-(IC1-TRIM1-Pad1)") (class "Default")
      (node (ref "IC1") (pin "1") (pinfunction "TRIM1_1") (pintype "passive"))
    )
    (net (code "68") (name "unconnected-(IC1-TRIM2-Pad8)") (class "Default")
      (node (ref "IC1") (pin "8") (pinfunction "TRIM2_8") (pintype "passive"))
    )
    (net (code "69") (name "unconnected-(IC2-TRIM1-Pad1)") (class "Default")
      (node (ref "IC2") (pin "1") (pinfunction "TRIM1_1") (pintype "passive"))
    )
    (net (code "70") (name "unconnected-(IC2-TRIM2-Pad8)") (class "Default")
      (node (ref "IC2") (pin "8") (pinfunction "TRIM2_8") (pintype "passive"))
    )
    (net (code "71") (name "unconnected-(U$1-PG-Pad5)") (class "Default")
      (node (ref "U$1") (pin "5") (pinfunction "PG_5") (pintype "bidirectional"))
    )
    (net (code "72") (name "unconnected-(U$5-PG-Pad5)") (class "Default")
      (node (ref "U$5") (pin "5") (pinfunction "PG_5") (pintype "bidirectional"))
    )
    (net (code "73") (name "unconnected-(U$9-PG-Pad5)") (class "Default")
      (node (ref "U$9") (pin "5") (pinfunction "PG_5") (pintype "bidirectional"))
    )
  )
)
